# Swap_Plate.net
KiCad netlist of a schematic drawn in EasyEDA
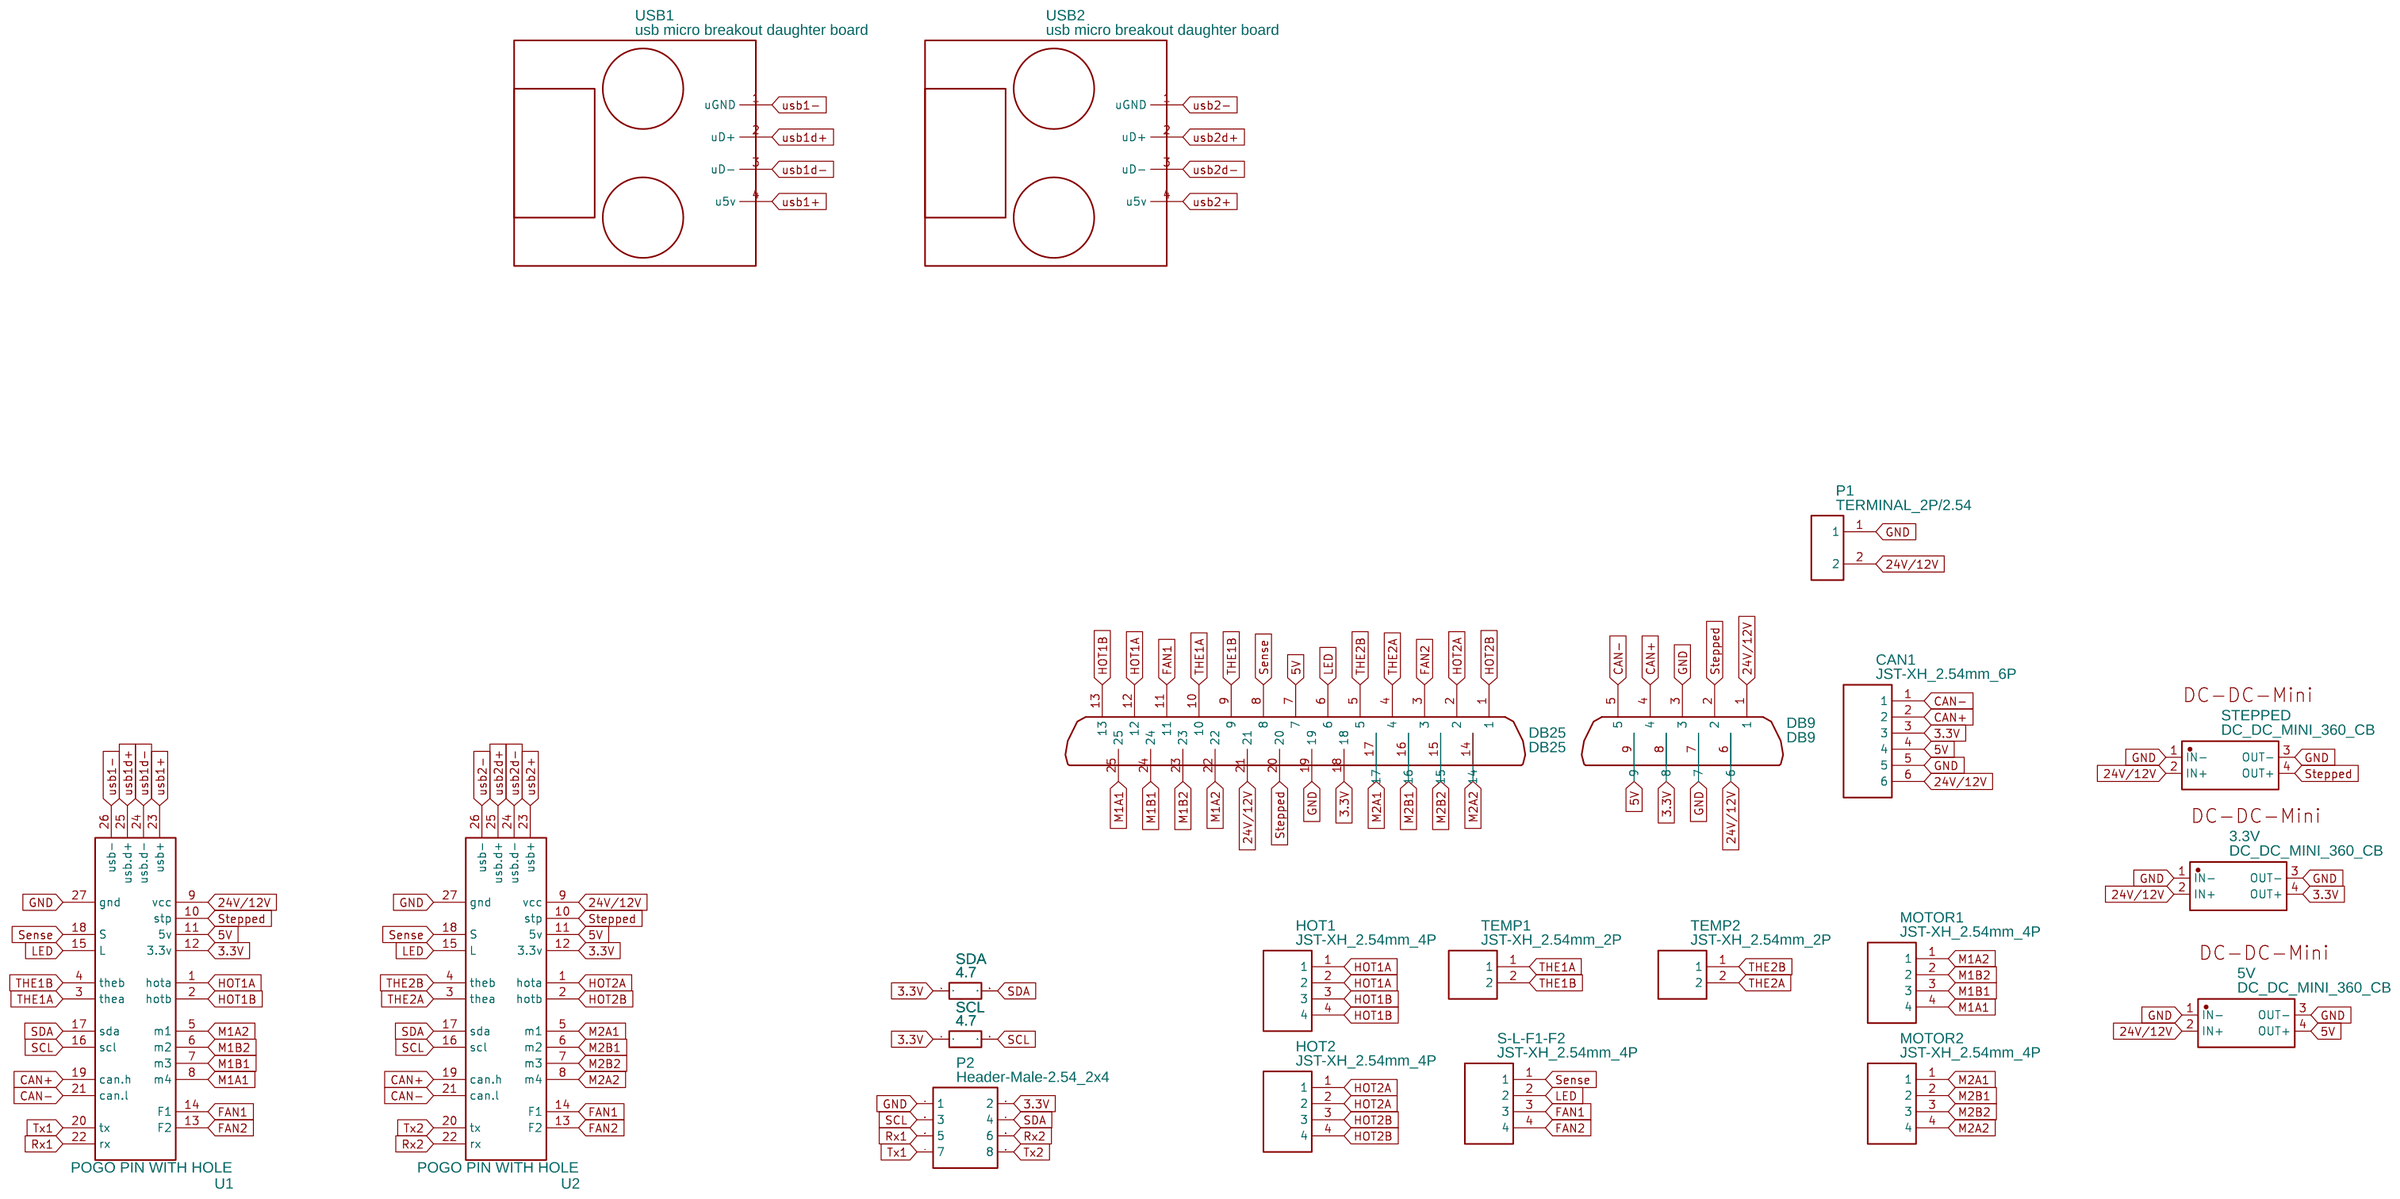
[diagram p0: schematic sheet]

(export (version "E")
  (design (tool "Eeschema 10.0.6"))
  (components
    (comp (ref "3.3V")
      (value "DC_DC_MINI_360_CB")
      (fields (field (name "BOM_Manufacturer Part") "Grobbling Sphincter"))
      (libsource (lib "") (part "DC_DC_MINI_360_CB_2"))
    )
    (comp (ref "5V")
      (value "DC_DC_MINI_360_CB")
      (fields (field (name "BOM_Manufacturer Part") "Grobbling Sphincter"))
      (libsource (lib "") (part "DC_DC_MINI_360_CB"))
    )
    (comp (ref "CAN1") (value "JST-XH_2.54mm_6P") (libsource (lib "") (part "JST-XH_2.54mm_6P")))
    (comp (ref "DB9") (value "DB9") (libsource (lib "") (part "DB9")))
    (comp (ref "DB25") (value "DB25") (libsource (lib "") (part "DB25")))
    (comp (ref "HOT1") (value "JST-XH_2.54mm_4P") (libsource (lib "") (part "JST-XH_2.54mm_4P")))
    (comp (ref "HOT2") (value "JST-XH_2.54mm_4P") (libsource (lib "") (part "JST-XH_2.54mm_4P")))
    (comp (ref "MOTOR1") (value "JST-XH_2.54mm_4P") (libsource (lib "") (part "JST-XH_2.54mm_4P_1")))
    (comp (ref "MOTOR2") (value "JST-XH_2.54mm_4P") (libsource (lib "") (part "JST-XH_2.54mm_4P_1")))
    (comp (ref "P1")
      (value "TERMINAL_2P/2.54")
      (fields (field (name "BOM_Manufacturer Part") "Screw terminal 2p"))
      (libsource (lib "") (part "TERMINAL_2P/2.54"))
    )
    (comp (ref "P2")
      (value "Header-Male-2.54_2x4")
      (fields
        (field (name "BOM_Manufacturer Part") "Header2X4P 2.54mm")
        (field (name "BOM_Supplier Part") "C58363")
      )
      (libsource (lib "") (part "Header-Male-2.54_2x4"))
    )
    (comp (ref "S-L-F1-F2") (value "JST-XH_2.54mm_4P") (libsource (lib "") (part "JST-XH_2.54mm_4P_2")))
    (comp (ref "SCL") (value "4.7") (libsource (lib "") (part "R_0603_EU_1")))
    (comp (ref "SDA") (value "4.7") (libsource (lib "") (part "R_0603_EU")))
    (comp (ref "STEPPED")
      (value "DC_DC_MINI_360_CB")
      (fields (field (name "BOM_Manufacturer Part") "Grobbling Sphincter"))
      (libsource (lib "") (part "DC_DC_MINI_360_CB_1"))
    )
    (comp (ref "TEMP1") (value "JST-XH_2.54mm_2P") (libsource (lib "") (part "JST-XH_2.54mm_2P")))
    (comp (ref "TEMP2") (value "JST-XH_2.54mm_2P") (libsource (lib "") (part "JST-XH_2.54mm_2P")))
    (comp (ref "U1") (value "POGO PIN WITH HOLE") (libsource (lib "") (part "POGO PIN WITH HOLE")))
    (comp (ref "U2") (value "POGO PIN WITH HOLE") (libsource (lib "") (part "POGO PIN WITH HOLE")))
    (comp (ref "USB1")
      (value "usb micro breakout daughter board")
      (libsource (lib "") (part "usb micro breakout daughter board"))
    )
    (comp (ref "USB2")
      (value "usb micro breakout daughter board")
      (libsource (lib "") (part "usb micro breakout daughter board"))
    )
  )
  (nets
    (net (code "1") (name "3.3V") (class "Default")
      (node (ref "3.3V") (pin "4") (pinfunction "OUT+_4") (pintype "unspecified"))
      (node (ref "CAN1") (pin "3") (pinfunction "3_3") (pintype "unspecified"))
      (node (ref "DB25") (pin "18") (pinfunction "18_18") (pintype "unspecified"))
      (node (ref "DB9") (pin "8") (pinfunction "8_8") (pintype "unspecified"))
      (node (ref "P2") (pin "2") (pinfunction "2_2") (pintype "input"))
      (node (ref "SCL") (pin "1") (pinfunction "1_1") (pintype "unspecified"))
      (node (ref "SDA") (pin "1") (pinfunction "1_1") (pintype "unspecified"))
      (node (ref "U1") (pin "12") (pinfunction "3.3v_12") (pintype "unspecified"))
      (node (ref "U2") (pin "12") (pinfunction "3.3v_12") (pintype "unspecified"))
    )
    (net (code "2") (name "5V") (class "Default")
      (node (ref "5V") (pin "4") (pinfunction "OUT+_4") (pintype "unspecified"))
      (node (ref "CAN1") (pin "4") (pinfunction "4_4") (pintype "unspecified"))
      (node (ref "DB25") (pin "7") (pinfunction "7_7") (pintype "unspecified"))
      (node (ref "DB9") (pin "9") (pinfunction "9_9") (pintype "unspecified"))
      (node (ref "U1") (pin "11") (pinfunction "5v_11") (pintype "unspecified"))
      (node (ref "U2") (pin "11") (pinfunction "5v_11") (pintype "unspecified"))
    )
    (net (code "3") (name "24V{slash}12V") (class "Default")
      (node (ref "3.3V") (pin "2") (pinfunction "IN+_2") (pintype "unspecified"))
      (node (ref "5V") (pin "2") (pinfunction "IN+_2") (pintype "unspecified"))
      (node (ref "CAN1") (pin "6") (pinfunction "6_6") (pintype "unspecified"))
      (node (ref "DB25") (pin "21") (pinfunction "21_21") (pintype "unspecified"))
      (node (ref "DB9") (pin "1") (pinfunction "1_1") (pintype "unspecified"))
      (node (ref "DB9") (pin "6") (pinfunction "6_6") (pintype "unspecified"))
      (node (ref "P1") (pin "2") (pinfunction "2_2") (pintype "unspecified"))
      (node (ref "STEPPED") (pin "2") (pinfunction "IN+_2") (pintype "unspecified"))
      (node (ref "U1") (pin "9") (pinfunction "vcc_9") (pintype "unspecified"))
      (node (ref "U2") (pin "9") (pinfunction "vcc_9") (pintype "unspecified"))
    )
    (net (code "4") (name "CAN+") (class "Default")
      (node (ref "CAN1") (pin "2") (pinfunction "2_2") (pintype "unspecified"))
      (node (ref "DB9") (pin "4") (pinfunction "4_4") (pintype "unspecified"))
      (node (ref "U1") (pin "19") (pinfunction "can.h_19") (pintype "unspecified"))
      (node (ref "U2") (pin "19") (pinfunction "can.h_19") (pintype "unspecified"))
    )
    (net (code "5") (name "CAN-") (class "Default")
      (node (ref "CAN1") (pin "1") (pinfunction "1_1") (pintype "unspecified"))
      (node (ref "DB9") (pin "5") (pinfunction "5_5") (pintype "unspecified"))
      (node (ref "U1") (pin "21") (pinfunction "can.l_21") (pintype "unspecified"))
      (node (ref "U2") (pin "21") (pinfunction "can.l_21") (pintype "unspecified"))
    )
    (net (code "6") (name "FAN1") (class "Default")
      (node (ref "DB25") (pin "11") (pinfunction "11_11") (pintype "unspecified"))
      (node (ref "S-L-F1-F2") (pin "3") (pinfunction "3_3") (pintype "unspecified"))
      (node (ref "U1") (pin "14") (pinfunction "F1_14") (pintype "unspecified"))
      (node (ref "U2") (pin "14") (pinfunction "F1_14") (pintype "unspecified"))
    )
    (net (code "7") (name "FAN2") (class "Default")
      (node (ref "DB25") (pin "3") (pinfunction "3_3") (pintype "unspecified"))
      (node (ref "S-L-F1-F2") (pin "4") (pinfunction "4_4") (pintype "unspecified"))
      (node (ref "U1") (pin "13") (pinfunction "F2_13") (pintype "unspecified"))
      (node (ref "U2") (pin "13") (pinfunction "F2_13") (pintype "unspecified"))
    )
    (net (code "8") (name "GND") (class "Default")
      (node (ref "3.3V") (pin "1") (pinfunction "IN-_1") (pintype "unspecified"))
      (node (ref "3.3V") (pin "3") (pinfunction "OUT-_3") (pintype "unspecified"))
      (node (ref "5V") (pin "1") (pinfunction "IN-_1") (pintype "unspecified"))
      (node (ref "5V") (pin "3") (pinfunction "OUT-_3") (pintype "unspecified"))
      (node (ref "CAN1") (pin "5") (pinfunction "5_5") (pintype "unspecified"))
      (node (ref "DB25") (pin "19") (pinfunction "19_19") (pintype "unspecified"))
      (node (ref "DB9") (pin "3") (pinfunction "3_3") (pintype "unspecified"))
      (node (ref "DB9") (pin "7") (pinfunction "7_7") (pintype "unspecified"))
      (node (ref "P1") (pin "1") (pinfunction "1_1") (pintype "unspecified"))
      (node (ref "P2") (pin "1") (pinfunction "1_1") (pintype "input"))
      (node (ref "STEPPED") (pin "1") (pinfunction "IN-_1") (pintype "unspecified"))
      (node (ref "STEPPED") (pin "3") (pinfunction "OUT-_3") (pintype "unspecified"))
      (node (ref "U1") (pin "27") (pinfunction "gnd_27") (pintype "unspecified"))
      (node (ref "U2") (pin "27") (pinfunction "gnd_27") (pintype "unspecified"))
    )
    (net (code "9") (name "HOT1A") (class "Default")
      (node (ref "DB25") (pin "12") (pinfunction "12_12") (pintype "unspecified"))
      (node (ref "HOT1") (pin "1") (pinfunction "1_1") (pintype "unspecified"))
      (node (ref "HOT1") (pin "2") (pinfunction "2_2") (pintype "unspecified"))
      (node (ref "U1") (pin "1") (pinfunction "hota_1") (pintype "unspecified"))
    )
    (net (code "10") (name "HOT1B") (class "Default")
      (node (ref "DB25") (pin "13") (pinfunction "13_13") (pintype "unspecified"))
      (node (ref "HOT1") (pin "3") (pinfunction "3_3") (pintype "unspecified"))
      (node (ref "HOT1") (pin "4") (pinfunction "4_4") (pintype "unspecified"))
      (node (ref "U1") (pin "2") (pinfunction "hotb_2") (pintype "unspecified"))
    )
    (net (code "11") (name "HOT2A") (class "Default")
      (node (ref "DB25") (pin "2") (pinfunction "2_2") (pintype "unspecified"))
      (node (ref "HOT2") (pin "1") (pinfunction "1_1") (pintype "unspecified"))
      (node (ref "HOT2") (pin "2") (pinfunction "2_2") (pintype "unspecified"))
      (node (ref "U2") (pin "1") (pinfunction "hota_1") (pintype "unspecified"))
    )
    (net (code "12") (name "HOT2B") (class "Default")
      (node (ref "DB25") (pin "1") (pinfunction "1_1") (pintype "unspecified"))
      (node (ref "HOT2") (pin "3") (pinfunction "3_3") (pintype "unspecified"))
      (node (ref "HOT2") (pin "4") (pinfunction "4_4") (pintype "unspecified"))
      (node (ref "U2") (pin "2") (pinfunction "hotb_2") (pintype "unspecified"))
    )
    (net (code "13") (name "LED") (class "Default")
      (node (ref "DB25") (pin "6") (pinfunction "6_6") (pintype "unspecified"))
      (node (ref "S-L-F1-F2") (pin "2") (pinfunction "2_2") (pintype "unspecified"))
      (node (ref "U1") (pin "15") (pinfunction "L_15") (pintype "unspecified"))
      (node (ref "U2") (pin "15") (pinfunction "L_15") (pintype "unspecified"))
    )
    (net (code "14") (name "M1A1") (class "Default")
      (node (ref "DB25") (pin "25") (pinfunction "25_25") (pintype "unspecified"))
      (node (ref "MOTOR1") (pin "4") (pinfunction "4_4") (pintype "unspecified"))
      (node (ref "U1") (pin "8") (pinfunction "m4_8") (pintype "unspecified"))
    )
    (net (code "15") (name "M1A2") (class "Default")
      (node (ref "DB25") (pin "22") (pinfunction "22_22") (pintype "unspecified"))
      (node (ref "MOTOR1") (pin "1") (pinfunction "1_1") (pintype "unspecified"))
      (node (ref "U1") (pin "5") (pinfunction "m1_5") (pintype "unspecified"))
    )
    (net (code "16") (name "M1B1") (class "Default")
      (node (ref "DB25") (pin "24") (pinfunction "24_24") (pintype "unspecified"))
      (node (ref "MOTOR1") (pin "3") (pinfunction "3_3") (pintype "unspecified"))
      (node (ref "U1") (pin "7") (pinfunction "m3_7") (pintype "unspecified"))
    )
    (net (code "17") (name "M1B2") (class "Default")
      (node (ref "DB25") (pin "23") (pinfunction "23_23") (pintype "unspecified"))
      (node (ref "MOTOR1") (pin "2") (pinfunction "2_2") (pintype "unspecified"))
      (node (ref "U1") (pin "6") (pinfunction "m2_6") (pintype "unspecified"))
    )
    (net (code "18") (name "M2A1") (class "Default")
      (node (ref "DB25") (pin "17") (pinfunction "17_17") (pintype "unspecified"))
      (node (ref "MOTOR2") (pin "1") (pinfunction "1_1") (pintype "unspecified"))
      (node (ref "U2") (pin "5") (pinfunction "m1_5") (pintype "unspecified"))
    )
    (net (code "19") (name "M2A2") (class "Default")
      (node (ref "DB25") (pin "14") (pinfunction "14_14") (pintype "unspecified"))
      (node (ref "MOTOR2") (pin "4") (pinfunction "4_4") (pintype "unspecified"))
      (node (ref "U2") (pin "8") (pinfunction "m4_8") (pintype "unspecified"))
    )
    (net (code "20") (name "M2B1") (class "Default")
      (node (ref "DB25") (pin "16") (pinfunction "16_16") (pintype "unspecified"))
      (node (ref "MOTOR2") (pin "2") (pinfunction "2_2") (pintype "unspecified"))
      (node (ref "U2") (pin "6") (pinfunction "m2_6") (pintype "unspecified"))
    )
    (net (code "21") (name "M2B2") (class "Default")
      (node (ref "DB25") (pin "15") (pinfunction "15_15") (pintype "unspecified"))
      (node (ref "MOTOR2") (pin "3") (pinfunction "3_3") (pintype "unspecified"))
      (node (ref "U2") (pin "7") (pinfunction "m3_7") (pintype "unspecified"))
    )
    (net (code "22") (name "Rx1") (class "Default")
      (node (ref "P2") (pin "5") (pinfunction "5_5") (pintype "input"))
      (node (ref "U1") (pin "22") (pinfunction "rx_22") (pintype "unspecified"))
    )
    (net (code "23") (name "Rx2") (class "Default")
      (node (ref "P2") (pin "6") (pinfunction "6_6") (pintype "input"))
      (node (ref "U2") (pin "22") (pinfunction "rx_22") (pintype "unspecified"))
    )
    (net (code "24") (name "SCL") (class "Default")
      (node (ref "P2") (pin "3") (pinfunction "3_3") (pintype "input"))
      (node (ref "SCL") (pin "2") (pinfunction "2_2") (pintype "unspecified"))
      (node (ref "U1") (pin "16") (pinfunction "scl_16") (pintype "unspecified"))
      (node (ref "U2") (pin "16") (pinfunction "scl_16") (pintype "unspecified"))
    )
    (net (code "25") (name "SDA") (class "Default")
      (node (ref "P2") (pin "4") (pinfunction "4_4") (pintype "input"))
      (node (ref "SDA") (pin "2") (pinfunction "2_2") (pintype "unspecified"))
      (node (ref "U1") (pin "17") (pinfunction "sda_17") (pintype "unspecified"))
      (node (ref "U2") (pin "17") (pinfunction "sda_17") (pintype "unspecified"))
    )
    (net (code "26") (name "Sense") (class "Default")
      (node (ref "DB25") (pin "8") (pinfunction "8_8") (pintype "unspecified"))
      (node (ref "S-L-F1-F2") (pin "1") (pinfunction "1_1") (pintype "unspecified"))
      (node (ref "U1") (pin "18") (pinfunction "S_18") (pintype "unspecified"))
      (node (ref "U2") (pin "18") (pinfunction "S_18") (pintype "unspecified"))
    )
    (net (code "27") (name "Stepped") (class "Default")
      (node (ref "DB25") (pin "20") (pinfunction "20_20") (pintype "unspecified"))
      (node (ref "DB9") (pin "2") (pinfunction "2_2") (pintype "unspecified"))
      (node (ref "STEPPED") (pin "4") (pinfunction "OUT+_4") (pintype "unspecified"))
      (node (ref "U1") (pin "10") (pinfunction "stp_10") (pintype "unspecified"))
      (node (ref "U2") (pin "10") (pinfunction "stp_10") (pintype "unspecified"))
    )
    (net (code "28") (name "THE1A") (class "Default")
      (node (ref "DB25") (pin "10") (pinfunction "10_10") (pintype "unspecified"))
      (node (ref "TEMP1") (pin "1") (pinfunction "1_1") (pintype "unspecified"))
      (node (ref "U1") (pin "3") (pinfunction "thea_3") (pintype "unspecified"))
    )
    (net (code "29") (name "THE1B") (class "Default")
      (node (ref "DB25") (pin "9") (pinfunction "9_9") (pintype "unspecified"))
      (node (ref "TEMP1") (pin "2") (pinfunction "2_2") (pintype "unspecified"))
      (node (ref "U1") (pin "4") (pinfunction "theb_4") (pintype "unspecified"))
    )
    (net (code "30") (name "THE2A") (class "Default")
      (node (ref "DB25") (pin "4") (pinfunction "4_4") (pintype "unspecified"))
      (node (ref "TEMP2") (pin "2") (pinfunction "2_2") (pintype "unspecified"))
      (node (ref "U2") (pin "3") (pinfunction "thea_3") (pintype "unspecified"))
    )
    (net (code "31") (name "THE2B") (class "Default")
      (node (ref "DB25") (pin "5") (pinfunction "5_5") (pintype "unspecified"))
      (node (ref "TEMP2") (pin "1") (pinfunction "1_1") (pintype "unspecified"))
      (node (ref "U2") (pin "4") (pinfunction "theb_4") (pintype "unspecified"))
    )
    (net (code "32") (name "Tx1") (class "Default")
      (node (ref "P2") (pin "7") (pinfunction "7_7") (pintype "input"))
      (node (ref "U1") (pin "20") (pinfunction "tx_20") (pintype "unspecified"))
    )
    (net (code "33") (name "Tx2") (class "Default")
      (node (ref "P2") (pin "8") (pinfunction "8_8") (pintype "input"))
      (node (ref "U2") (pin "20") (pinfunction "tx_20") (pintype "unspecified"))
    )
    (net (code "34") (name "usb1+") (class "Default")
      (node (ref "U1") (pin "23") (pinfunction "usb+_23") (pintype "unspecified"))
      (node (ref "USB1") (pin "4") (pinfunction "u5v_4") (pintype "unspecified"))
    )
    (net (code "35") (name "usb1-") (class "Default")
      (node (ref "U1") (pin "26") (pinfunction "usb-_26") (pintype "unspecified"))
      (node (ref "USB1") (pin "1") (pinfunction "uGND_1") (pintype "unspecified"))
    )
    (net (code "36") (name "usb1d+") (class "Default")
      (node (ref "U1") (pin "25") (pinfunction "usb.d+_25") (pintype "unspecified"))
      (node (ref "USB1") (pin "2") (pinfunction "uD+_2") (pintype "unspecified"))
    )
    (net (code "37") (name "usb1d-") (class "Default")
      (node (ref "U1") (pin "24") (pinfunction "usb.d-_24") (pintype "unspecified"))
      (node (ref "USB1") (pin "3") (pinfunction "uD-_3") (pintype "unspecified"))
    )
    (net (code "38") (name "usb2+") (class "Default")
      (node (ref "U2") (pin "23") (pinfunction "usb+_23") (pintype "unspecified"))
      (node (ref "USB2") (pin "4") (pinfunction "u5v_4") (pintype "unspecified"))
    )
    (net (code "39") (name "usb2-") (class "Default")
      (node (ref "U2") (pin "26") (pinfunction "usb-_26") (pintype "unspecified"))
      (node (ref "USB2") (pin "1") (pinfunction "uGND_1") (pintype "unspecified"))
    )
    (net (code "40") (name "usb2d+") (class "Default")
      (node (ref "U2") (pin "25") (pinfunction "usb.d+_25") (pintype "unspecified"))
      (node (ref "USB2") (pin "2") (pinfunction "uD+_2") (pintype "unspecified"))
    )
    (net (code "41") (name "usb2d-") (class "Default")
      (node (ref "U2") (pin "24") (pinfunction "usb.d-_24") (pintype "unspecified"))
      (node (ref "USB2") (pin "3") (pinfunction "uD-_3") (pintype "unspecified"))
    )
  )
)
